# SMC-DCc5.net
KiCad netlist of a schematic drawn in EAGLE
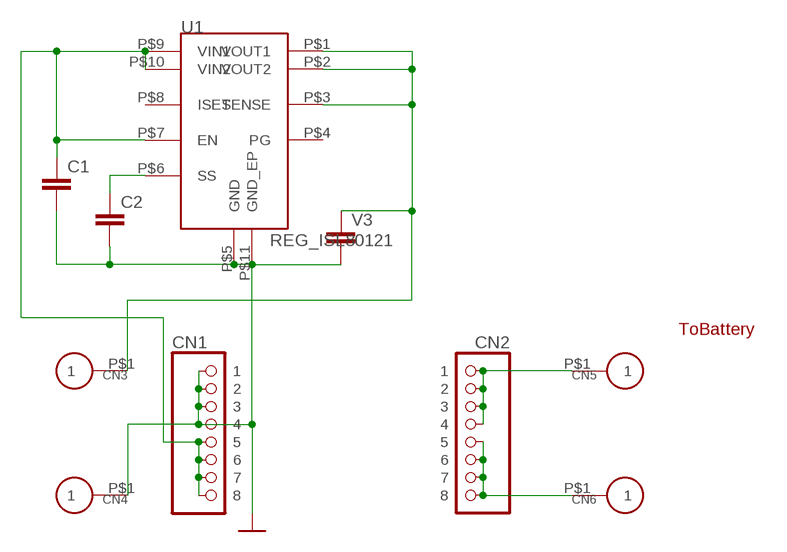
[diagram p0: schematic, sheet 1]

(export (version "E")
  (design (tool "Eeschema 10.0.6"))
  (components
    (comp (ref "C1")
      (value "CAP0603")
      (footprint "eagle-import:0603")
      (libsource (lib "eagle-import") (part "CAP0603"))
    )
    (comp (ref "C2")
      (value "CAP0603")
      (footprint "eagle-import:0603")
      (libsource (lib "eagle-import") (part "CAP0603"))
    )
    (comp (ref "CN1")
      (value "CON_PINHD-1X8FPC05")
      (footprint "eagle-import:CON_8P_FPC05MM")
      (libsource (lib "eagle-import") (part "CON_PINHD-1X8FPC05"))
    )
    (comp (ref "CN2")
      (value "CON_PINHD-1X8FPC05")
      (footprint "eagle-import:CON_8P_FPC05MM")
      (libsource (lib "eagle-import") (part "CON_PINHD-1X8FPC05"))
    )
    (comp (ref "CN3")
      (value "CON_P01SMD1MM")
      (footprint "eagle-import:PAD_SMD1MM")
      (libsource (lib "eagle-import") (part "CON_P01SMD1MM"))
    )
    (comp (ref "CN4")
      (value "CON_P01SMD1MM")
      (footprint "eagle-import:PAD_SMD1MM")
      (libsource (lib "eagle-import") (part "CON_P01SMD1MM"))
    )
    (comp (ref "CN5")
      (value "CON_P01SMD1MM")
      (footprint "eagle-import:PAD_SMD1MM")
      (libsource (lib "eagle-import") (part "CON_P01SMD1MM"))
    )
    (comp (ref "CN6")
      (value "CON_P01SMD1MM")
      (footprint "eagle-import:PAD_SMD1MM")
      (libsource (lib "eagle-import") (part "CON_P01SMD1MM"))
    )
    (comp (ref "U1")
      (value "REG_ISL80121")
      (footprint "eagle-import:DFN10_0.5MM")
      (libsource (lib "eagle-import") (part "REG_ISL80121"))
    )
    (comp (ref "V3")
      (value "CAP1206")
      (footprint "eagle-import:1206")
      (libsource (lib "eagle-import") (part "CAP1206"))
    )
  )
  (nets
    (net (code "1") (name "Net-(CN1-5)") (class "Default")
      (node (ref "C1") (pin "1") (pinfunction "1_1") (pintype "passive"))
      (node (ref "CN1") (pin "P$5") (pinfunction "5_P$5") (pintype "passive"))
      (node (ref "CN1") (pin "P$6") (pinfunction "6_P$6") (pintype "passive"))
      (node (ref "CN1") (pin "P$7") (pinfunction "7_P$7") (pintype "passive"))
      (node (ref "CN1") (pin "P$8") (pinfunction "8_P$8") (pintype "passive"))
      (node (ref "U1") (pin "P$10") (pinfunction "VIN2_P$10") (pintype "bidirectional"))
      (node (ref "U1") (pin "P$7") (pinfunction "EN_P$7") (pintype "bidirectional"))
      (node (ref "U1") (pin "P$9") (pinfunction "VIN1_P$9") (pintype "bidirectional"))
    )
    (net (code "2") (name "Net-(CN2-1)") (class "Default")
      (node (ref "CN2") (pin "P$1") (pinfunction "1_P$1") (pintype "passive"))
      (node (ref "CN2") (pin "P$2") (pinfunction "2_P$2") (pintype "passive"))
      (node (ref "CN2") (pin "P$3") (pinfunction "3_P$3") (pintype "passive"))
      (node (ref "CN2") (pin "P$4") (pinfunction "4_P$4") (pintype "passive"))
      (node (ref "CN5") (pin "P$1") (pinfunction "1_P$1") (pintype "bidirectional"))
    )
    (net (code "3") (name "Net-(CN2-5)") (class "Default")
      (node (ref "CN2") (pin "P$5") (pinfunction "5_P$5") (pintype "passive"))
      (node (ref "CN2") (pin "P$6") (pinfunction "6_P$6") (pintype "passive"))
      (node (ref "CN2") (pin "P$7") (pinfunction "7_P$7") (pintype "passive"))
      (node (ref "CN2") (pin "P$8") (pinfunction "8_P$8") (pintype "passive"))
      (node (ref "CN6") (pin "P$1") (pinfunction "1_P$1") (pintype "bidirectional"))
    )
    (net (code "4") (name "Net-(CN3-1)") (class "Default")
      (node (ref "CN3") (pin "P$1") (pinfunction "1_P$1") (pintype "bidirectional"))
      (node (ref "U1") (pin "P$1") (pinfunction "VOUT1_P$1") (pintype "bidirectional"))
      (node (ref "U1") (pin "P$2") (pinfunction "VOUT2_P$2") (pintype "bidirectional"))
      (node (ref "U1") (pin "P$3") (pinfunction "SENSE_P$3") (pintype "bidirectional"))
      (node (ref "V3") (pin "P$1") (pinfunction "1_P$1") (pintype "passive"))
    )
    (net (code "5") (name "Net-(U1-SS)") (class "Default")
      (node (ref "C2") (pin "1") (pinfunction "1_1") (pintype "passive"))
      (node (ref "U1") (pin "P$6") (pinfunction "SS_P$6") (pintype "bidirectional"))
    )
    (net (code "6") (name "POW_GND") (class "Default")
      (node (ref "C1") (pin "2") (pinfunction "2_2") (pintype "passive"))
      (node (ref "C2") (pin "2") (pinfunction "2_2") (pintype "passive"))
      (node (ref "CN1") (pin "P$1") (pinfunction "1_P$1") (pintype "passive"))
      (node (ref "CN1") (pin "P$2") (pinfunction "2_P$2") (pintype "passive"))
      (node (ref "CN1") (pin "P$3") (pinfunction "3_P$3") (pintype "passive"))
      (node (ref "CN1") (pin "P$4") (pinfunction "4_P$4") (pintype "passive"))
      (node (ref "CN4") (pin "P$1") (pinfunction "1_P$1") (pintype "bidirectional"))
      (node (ref "U1") (pin "P$11") (pinfunction "GND_EP_P$11") (pintype "bidirectional"))
      (node (ref "U1") (pin "P$5") (pinfunction "GND_P$5") (pintype "bidirectional"))
      (node (ref "V3") (pin "P$2") (pinfunction "2_P$2") (pintype "passive"))
    )
    (net (code "7") (name "unconnected-(U1-ISET-PadP$8)") (class "Default")
      (node (ref "U1") (pin "P$8") (pinfunction "ISET_P$8") (pintype "bidirectional"))
    )
    (net (code "8") (name "unconnected-(U1-PG-PadP$4)") (class "Default")
      (node (ref "U1") (pin "P$4") (pinfunction "PG_P$4") (pintype "bidirectional"))
    )
  )
)
